# TDA-sma_rev2.net
KiCad netlist of a schematic drawn in Altium Designer
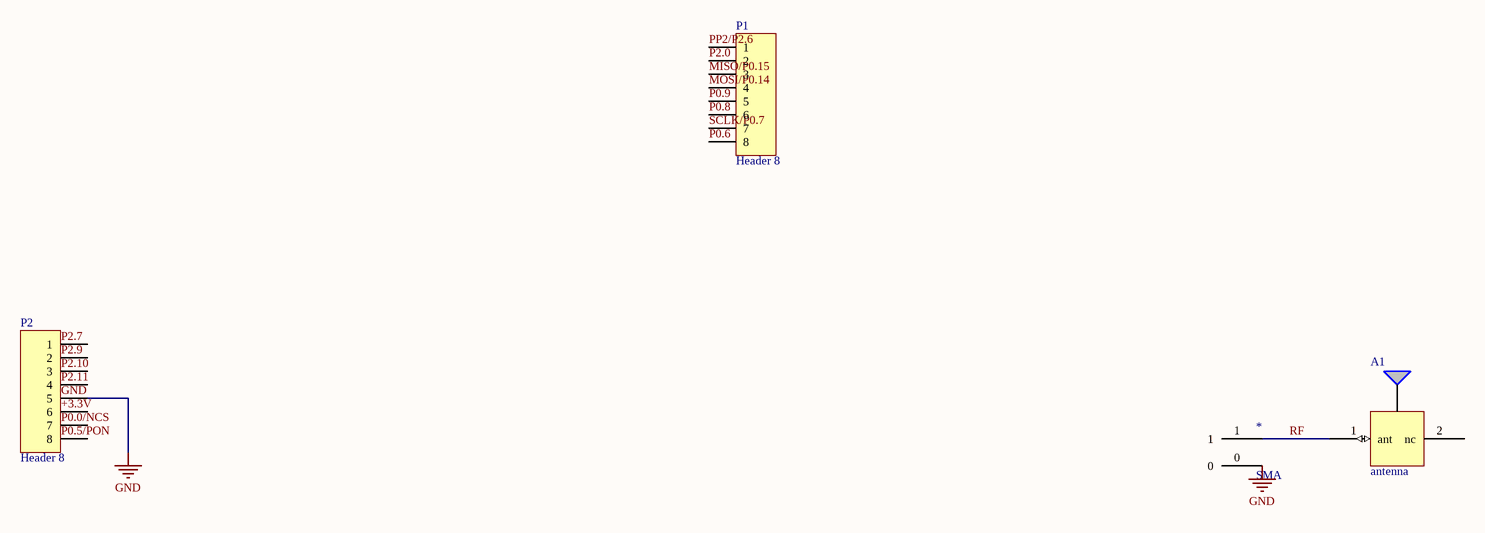
[diagram p0: TDA-sma_rev2.SchDoc]

(export (version "E")
  (design (tool "Eeschema 10.0.6"))
  (components
    (comp (ref "*") (value "SMA") (footprint "SMA") (libsource (lib "Schlib1_rev2") (part "SMA")))
    (comp (ref "A1")
      (value "antenna")
      (footprint "Chip Antenna")
      (libsource (lib "Schlib1") (part "antenna"))
    )
    (comp (ref "P1")
      (value "Header 8")
      (footprint "HDR1X8")
      (description "Header, 8-Pin")
      (fields (field (name "PUBLISHER") "Altium Limited"))
      (libsource (lib "Miscellaneous Connectors") (part "Header 8"))
    )
    (comp (ref "P2")
      (value "Header 8")
      (footprint "HDR1X8")
      (description "Header, 8-Pin")
      (fields (field (name "PUBLISHER") "Altium Limited"))
      (libsource (lib "") (part "Header 8_1"))
    )
  )
  (nets
    (net (code "2") (name "/MISO{slash}P0.15") (class "Default")
      (node (ref "P1") (pin "3") (pinfunction "3_3") (pintype "passive"))
    )
    (net (code "3") (name "/MOSI{slash}P0.14") (class "Default")
      (node (ref "P1") (pin "4") (pinfunction "4_4") (pintype "passive"))
    )
    (net (code "6") (name "/P0.6") (class "Default")
      (node (ref "P1") (pin "8") (pinfunction "8_8") (pintype "passive"))
    )
    (net (code "7") (name "/P0.8") (class "Default")
      (node (ref "P1") (pin "6") (pinfunction "6_6") (pintype "passive"))
    )
    (net (code "8") (name "/P0.9") (class "Default")
      (node (ref "P1") (pin "5") (pinfunction "5_5") (pintype "passive"))
    )
    (net (code "9") (name "/P2.0") (class "Default")
      (node (ref "P1") (pin "2") (pinfunction "2_2") (pintype "passive"))
    )
    (net (code "14") (name "/PP2{slash}P2.6") (class "Default")
      (node (ref "P1") (pin "1") (pinfunction "1_1") (pintype "passive"))
    )
    (net (code "15") (name "/RF") (class "Default")
      (node (ref "*") (pin "1") (pinfunction "1_1") (pintype "passive"))
      (node (ref "A1") (pin "1") (pinfunction "ant_1") (pintype "bidirectional"))
    )
    (net (code "16") (name "/SCLK{slash}P0.7") (class "Default")
      (node (ref "P1") (pin "7") (pinfunction "7_7") (pintype "passive"))
    )
    (net (code "17") (name "GND") (class "Default")
      (node (ref "*") (pin "0") (pinfunction "0_0") (pintype "passive"))
      (node (ref "P2") (pin "5") (pinfunction "5_5") (pintype "passive"))
    )
    (net (code "18") (name "unconnected-(A1-nc-Pad2)") (class "Default")
      (node (ref "A1") (pin "2") (pinfunction "nc_2") (pintype "passive"))
    )
    (net (code "19") (name "unconnected-(P2-Pad1)") (class "Default")
      (node (ref "P2") (pin "1") (pinfunction "1_1") (pintype "passive"))
    )
    (net (code "20") (name "unconnected-(P2-Pad2)") (class "Default")
      (node (ref "P2") (pin "2") (pinfunction "2_2") (pintype "passive"))
    )
    (net (code "21") (name "unconnected-(P2-Pad3)") (class "Default")
      (node (ref "P2") (pin "3") (pinfunction "3_3") (pintype "passive"))
    )
    (net (code "22") (name "unconnected-(P2-Pad4)") (class "Default")
      (node (ref "P2") (pin "4") (pinfunction "4_4") (pintype "passive"))
    )
    (net (code "23") (name "unconnected-(P2-Pad6)") (class "Default")
      (node (ref "P2") (pin "6") (pinfunction "6_6") (pintype "passive"))
    )
    (net (code "24") (name "unconnected-(P2-Pad7)") (class "Default")
      (node (ref "P2") (pin "7") (pinfunction "7_7") (pintype "passive"))
    )
    (net (code "25") (name "unconnected-(P2-Pad8)") (class "Default")
      (node (ref "P2") (pin "8") (pinfunction "8_8") (pintype "passive"))
    )
  )
)
